# Reset.net
KiCad netlist of a schematic drawn in Altium Designer
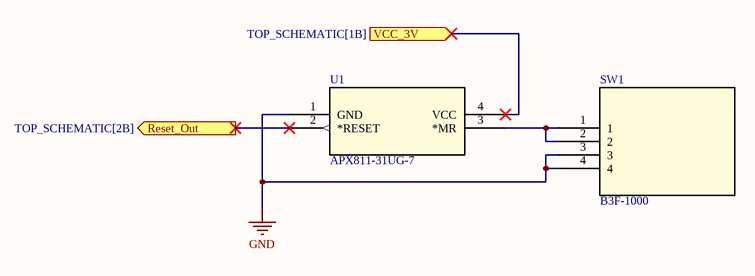
[diagram p0: Reset.SchDoc]

(export (version "E")
  (design (tool "Eeschema 10.0.6"))
  (components
    (comp (ref "SW1")
      (value "B3F-1000")
      (footprint "SW_B3F-1000_OMR")
      (description "Description")
      (fields (field (name "COPYRIGHT") "Copyright (C) 2026 Ultra Librarian. All rights reserved."))
      (libsource (lib "B3F-1000") (part "B3F-1000"))
    )
    (comp (ref "U1")
      (value "APX811-31UG-7")
      (footprint "APX811-31UG-7_DIO")
      (description "No Description Available")
      (fields (field (name "COPYRIGHT") "Copyright (C) 2026 Ultra Librarian. All rights reserved."))
      (libsource (lib "APX811-31UG-7") (part "APX811-31UG-7"))
    )
  )
  (nets
    (net (code "1") (name "/Reset_Out") (class "Default")
      (node (ref "U1") (pin "2") (pinfunction "*RESET_2") (pintype "output+no_connect"))
    )
    (net (code "2") (name "/VCC_3V") (class "Default")
      (node (ref "U1") (pin "4") (pinfunction "VCC_4") (pintype "power_in+no_connect"))
    )
    (net (code "3") (name "GND") (class "Default")
      (node (ref "SW1") (pin "3") (pinfunction "3_3") (pintype "passive"))
      (node (ref "SW1") (pin "4") (pinfunction "4_4") (pintype "passive"))
      (node (ref "U1") (pin "1") (pinfunction "GND_1") (pintype "power_in"))
    )
    (net (code "4") (name "Net-(U1-*MR)") (class "Default")
      (node (ref "SW1") (pin "1") (pinfunction "1_1") (pintype "passive"))
      (node (ref "SW1") (pin "2") (pinfunction "2_2") (pintype "passive"))
      (node (ref "U1") (pin "3") (pinfunction "*MR_3") (pintype "passive"))
    )
  )
)
